# HDMI.net
KiCad netlist of a schematic drawn in Altium Designer
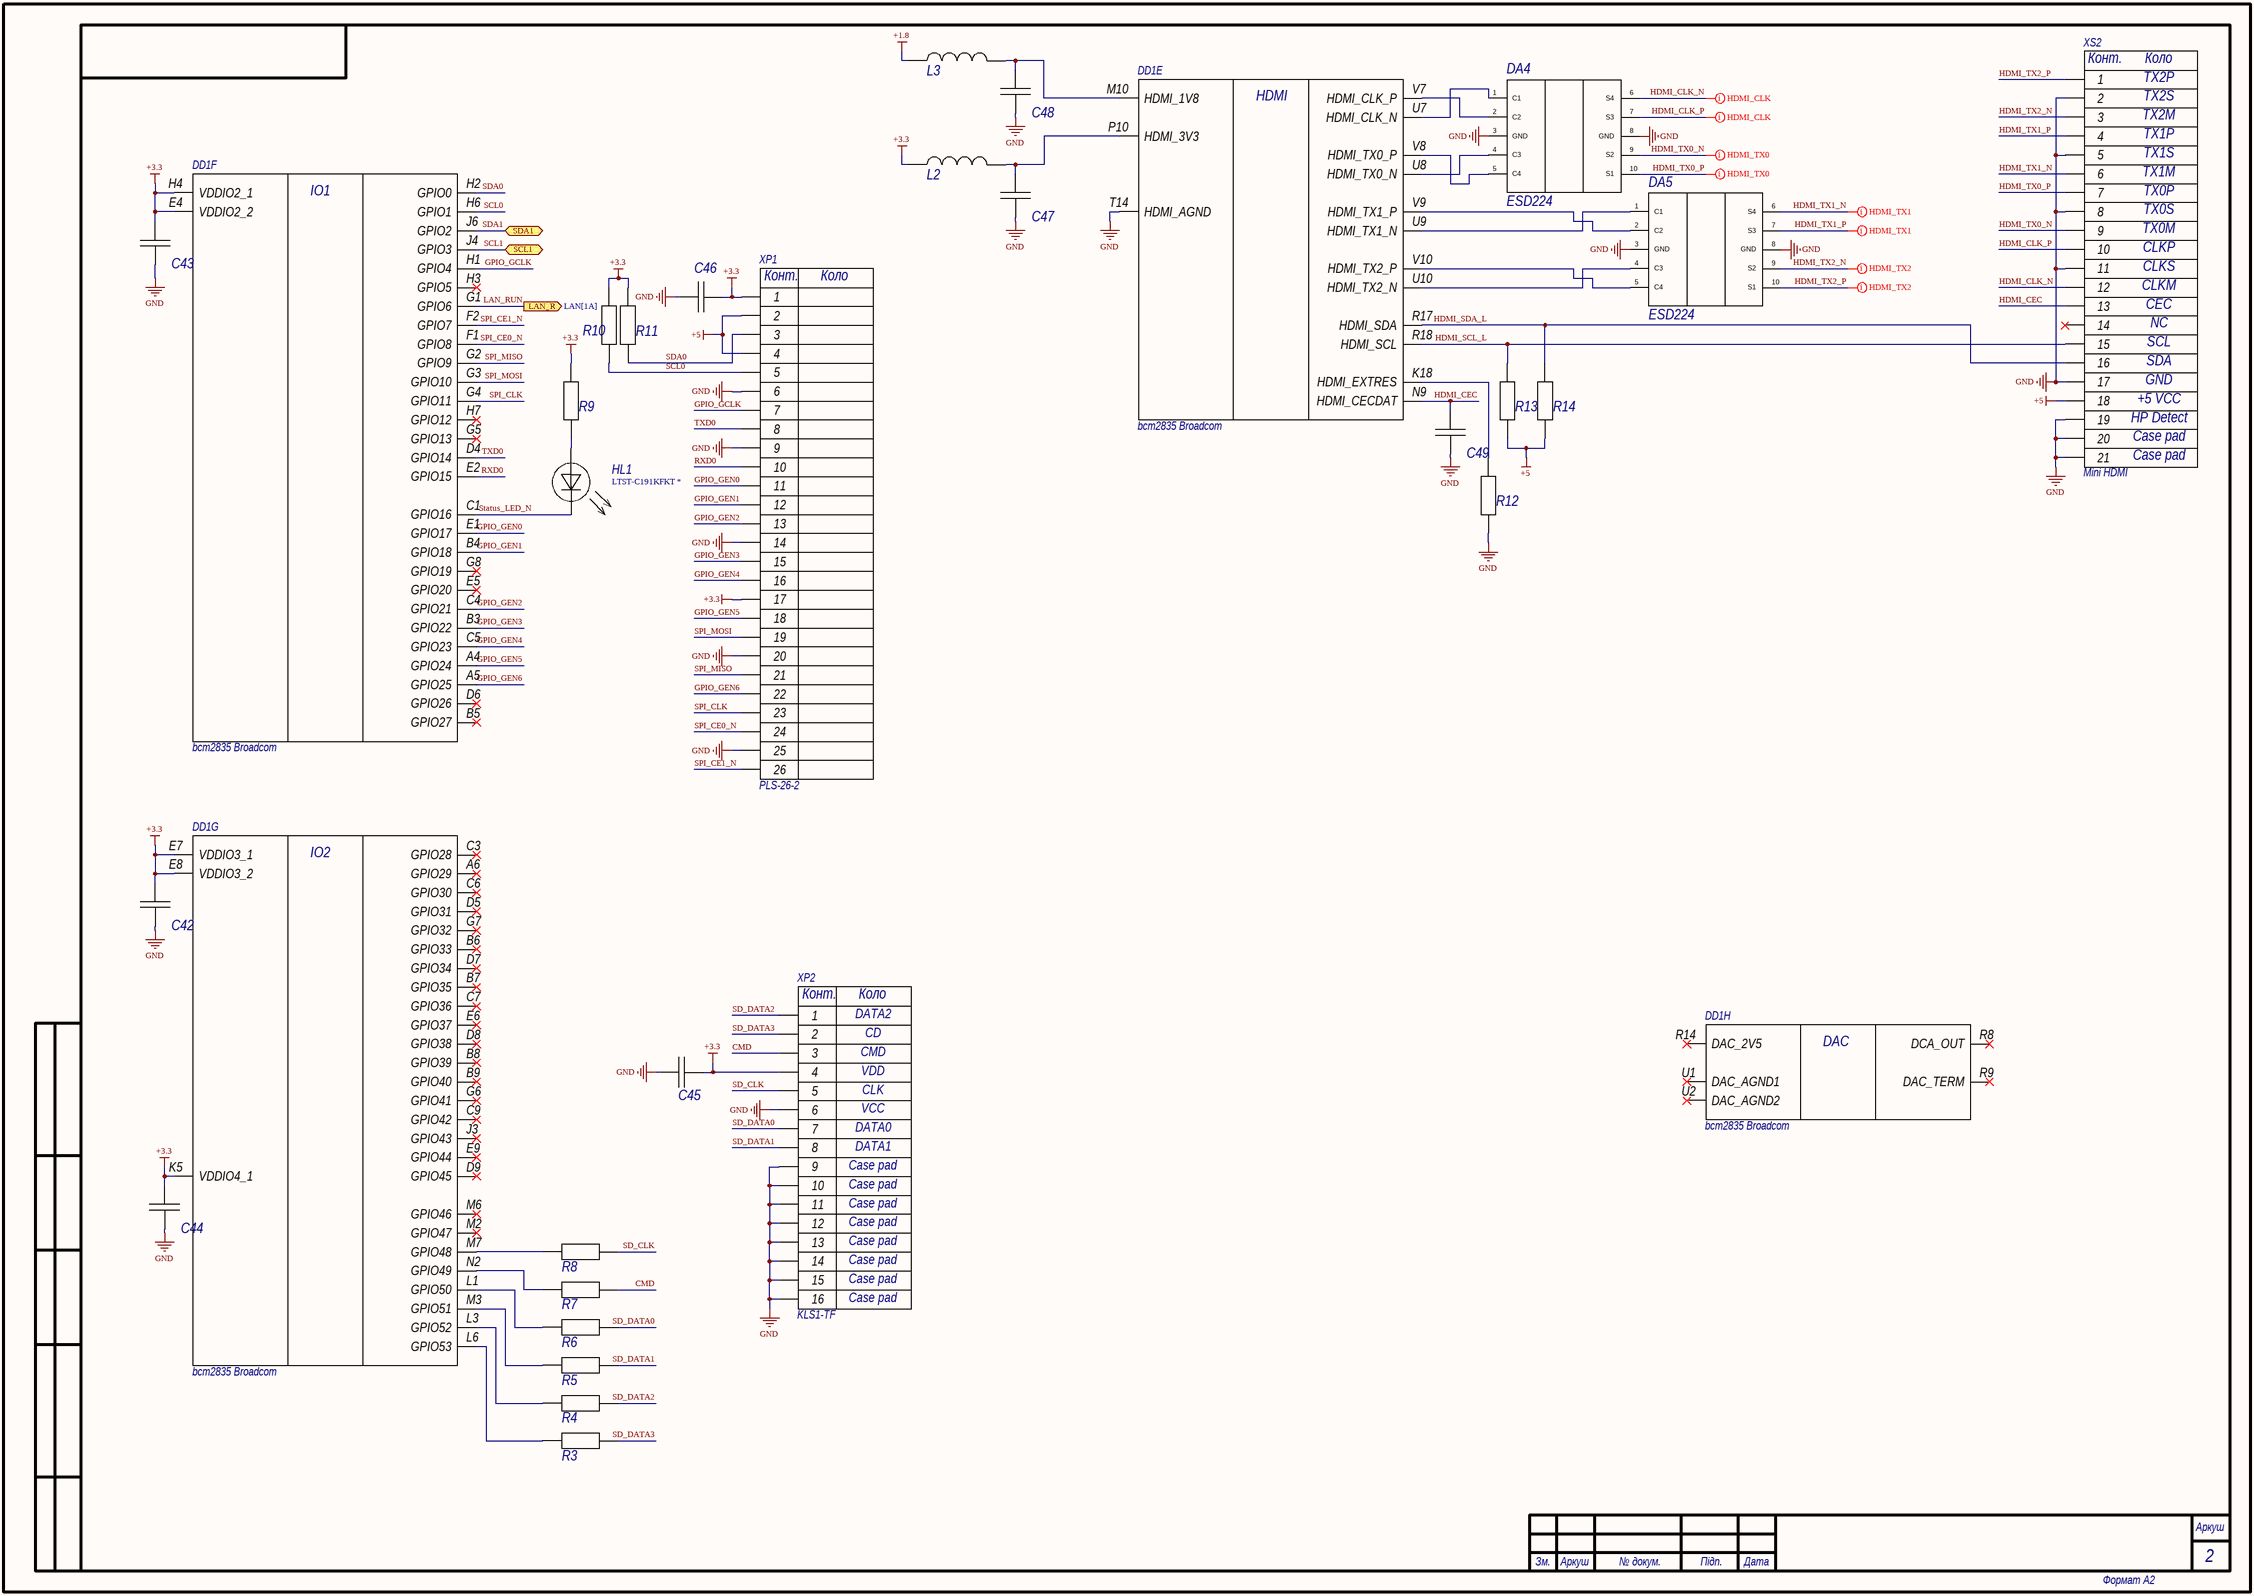
[diagram p0: HDMI.SchDoc]

(export (version "E")
  (design (tool "Eeschema 10.0.6"))
  (components
    (comp (ref "C42")
      (value "C-0603 * * * * *")
      (footprint "С-0603")
      (description "Generic")
      (libsource (lib "Schlib1") (part "С-0603"))
    )
    (comp (ref "C43")
      (value "C-0603 * * * * *")
      (footprint "С-0603")
      (description "Generic")
      (libsource (lib "Schlib1") (part "С-0603"))
    )
    (comp (ref "C44")
      (value "C-0603 * * * * *")
      (footprint "С-0603")
      (description "Generic")
      (libsource (lib "Schlib1") (part "С-0603"))
    )
    (comp (ref "C45")
      (value "C-0603 * * * * *")
      (footprint "С-0603")
      (description "Generic")
      (libsource (lib "Schlib1") (part "С-0603"))
    )
    (comp (ref "C46")
      (value "C-0603 * * * * *")
      (footprint "С-0603")
      (description "Generic")
      (libsource (lib "Schlib1") (part "С-0603"))
    )
    (comp (ref "C47")
      (value "C-0805 * * * * *")
      (footprint "C-0805-KEM")
      (description "Generic")
      (libsource (lib "Schlib1") (part "С-0805"))
    )
    (comp (ref "C48")
      (value "C-0805 * * * * *")
      (footprint "C-0805-KEM")
      (description "Generic")
      (libsource (lib "Schlib1") (part "С-0805"))
    )
    (comp (ref "C49")
      (value "C-0402 * * * * *")
      (footprint "C-0402")
      (description "Generic")
      (libsource (lib "Schlib1") (part "С-0402"))
    )
    (comp (ref "DA4")
      (value "ESD224 *")
      (footprint "DQA0010A")
      (description "bav99 double diode")
      (fields (field (name "NAME") "ESD224"))
      (libsource (lib "Schlib1") (part "ESD224"))
    )
    (comp (ref "DA5")
      (value "ESD224 *")
      (footprint "DQA0010A")
      (description "bav99 double diode")
      (fields (field (name "NAME") "ESD224"))
      (libsource (lib "Schlib1") (part "ESD224"))
    )
    (comp (ref "DD1")
      (value "bcm2835 Broadcom")
      (footprint "BGA81C65P18X18_1200X1200")
      (description "BCM2835 ARM-based processor")
      (fields (field (name "MANUFACTURER") "Broadcom"))
      (libsource (lib "Schlib1") (part "bcm2835"))
    )
    (comp (ref "HL1")
      (value "LTST-C191KFKT *")
      (footprint "LED_DIALIGHT_598_DIA")
      (description "Generic LED 0603")
      (libsource (lib "Schlib1") (part "LED 0603"))
    )
    (comp (ref "L2")
      (value "R-0402 * * * *")
      (footprint "FB-0805")
      (description "Generic")
      (libsource (lib "Schlib1") (part "Ferrite Bead 0805"))
    )
    (comp (ref "L3")
      (value "R-0402 * * * *")
      (footprint "FB-0805")
      (description "Generic")
      (libsource (lib "Schlib1") (part "Ferrite Bead 0805"))
    )
    (comp (ref "R3")
      (value "R-0603 * * * *")
      (footprint "R-0603")
      (description "Generic")
      (libsource (lib "Schlib1") (part "R-0603"))
    )
    (comp (ref "R4")
      (value "R-0603 * * * *")
      (footprint "R-0603")
      (description "Generic")
      (libsource (lib "Schlib1") (part "R-0603"))
    )
    (comp (ref "R5")
      (value "R-0603 * * * *")
      (footprint "R-0603")
      (description "Generic")
      (libsource (lib "Schlib1") (part "R-0603"))
    )
    (comp (ref "R6")
      (value "R-0603 * * * *")
      (footprint "R-0603")
      (description "Generic")
      (libsource (lib "Schlib1") (part "R-0603"))
    )
    (comp (ref "R7")
      (value "R-0603 * * * *")
      (footprint "R-0603")
      (description "Generic")
      (libsource (lib "Schlib1") (part "R-0603"))
    )
    (comp (ref "R8")
      (value "R-0603 * * * *")
      (footprint "R-0603")
      (description "Generic")
      (libsource (lib "Schlib1") (part "R-0603"))
    )
    (comp (ref "R9")
      (value "R-0603 * * * *")
      (footprint "R-0603")
      (description "Generic")
      (libsource (lib "") (part "R-0603_1"))
    )
    (comp (ref "R10")
      (value "R-0402 * * * *")
      (footprint "R-0402")
      (description "Generic")
      (libsource (lib "") (part "R-0402_1"))
    )
    (comp (ref "R11")
      (value "R-0402 * * * *")
      (footprint "R-0402")
      (description "Generic")
      (libsource (lib "") (part "R-0402_1"))
    )
    (comp (ref "R12")
      (value "R-0402 * * * *")
      (footprint "R-0402")
      (description "Generic")
      (libsource (lib "") (part "R-0402_1"))
    )
    (comp (ref "R13")
      (value "R-0402 * * * *")
      (footprint "R-0402")
      (description "Generic")
      (libsource (lib "Schlib1") (part "R-0402"))
    )
    (comp (ref "R14")
      (value "R-0402 * * * *")
      (footprint "R-0402")
      (description "Generic")
      (libsource (lib "Schlib1") (part "R-0402"))
    )
    (comp (ref "XP1")
      (value "PLS-26-2")
      (footprint "26 pin 2.54mm pitch 2 row")
      (description "PLS connector 26 pin 2.54mm pitch 2 rows")
      (libsource (lib "Schlib1") (part "PLS-26-2"))
    )
    (comp (ref "XP2")
      (value "KLS1-TF")
      (footprint "504077-1891_MOL")
      (description "Micro-SD card connector SMT mounting")
      (libsource (lib "Schlib1") (part "kls1-tf"))
    )
    (comp (ref "XS2")
      (value "Mini HDMI")
      (footprint "mini HDMI")
      (libsource (lib "Schlib1") (part "Mini HDMI"))
    )
  )
  (nets
    (net (code "1") (name "+1.8") (class "Default")
      (node (ref "L3") (pin "1") (pinfunction "1_1") (pintype "passive"))
    )
    (net (code "2") (name "+3.3") (class "Default")
      (node (ref "C42") (pin "1") (pinfunction "1_1") (pintype "passive"))
      (node (ref "C43") (pin "2") (pinfunction "2_2") (pintype "passive"))
      (node (ref "C44") (pin "1") (pinfunction "1_1") (pintype "passive"))
      (node (ref "C45") (pin "1") (pinfunction "1_1") (pintype "passive"))
      (node (ref "C46") (pin "2") (pinfunction "2_2") (pintype "passive"))
      (node (ref "DD1") (pin "E4") (pinfunction "VDDIO2_2_E4") (pintype "passive"))
      (node (ref "DD1") (pin "E7") (pinfunction "VDDIO3_1_E7") (pintype "passive"))
      (node (ref "DD1") (pin "E8") (pinfunction "VDDIO3_2_E8") (pintype "passive"))
      (node (ref "DD1") (pin "H4") (pinfunction "VDDIO2_1_H4") (pintype "passive"))
      (node (ref "DD1") (pin "K5") (pinfunction "VDDIO4_1_K5") (pintype "passive"))
      (node (ref "L2") (pin "1") (pinfunction "1_1") (pintype "passive"))
      (node (ref "R10") (pin "2") (pinfunction "2_2") (pintype "passive"))
      (node (ref "R11") (pin "2") (pinfunction "2_2") (pintype "passive"))
      (node (ref "R9") (pin "2") (pinfunction "2_2") (pintype "passive"))
      (node (ref "XP1") (pin "1") (pinfunction "1_1") (pintype "passive"))
      (node (ref "XP1") (pin "17") (pinfunction "17_17") (pintype "passive"))
      (node (ref "XP2") (pin "4") (pinfunction "4_4") (pintype "passive"))
    )
    (net (code "3") (name "+5") (class "Default")
      (node (ref "R13") (pin "2") (pinfunction "2_2") (pintype "passive"))
      (node (ref "R14") (pin "2") (pinfunction "2_2") (pintype "passive"))
      (node (ref "XP1") (pin "2") (pinfunction "2_2") (pintype "passive"))
      (node (ref "XP1") (pin "4") (pinfunction "4_4") (pintype "passive"))
      (node (ref "XS2") (pin "18") (pinfunction "18_18") (pintype "passive"))
    )
    (net (code "4") (name "/CMD") (class "Default")
      (node (ref "R7") (pin "2") (pinfunction "2_2") (pintype "passive"))
      (node (ref "XP2") (pin "3") (pinfunction "3_3") (pintype "passive"))
    )
    (net (code "5") (name "/GPIO_GCLK") (class "Default")
      (node (ref "DD1") (pin "H1") (pinfunction "GPIO4_H1") (pintype "passive"))
      (node (ref "XP1") (pin "7") (pinfunction "7_7") (pintype "passive"))
    )
    (net (code "6") (name "/GPIO_GEN0") (class "Default")
      (node (ref "DD1") (pin "E1") (pinfunction "GPIO17_E1") (pintype "passive"))
      (node (ref "XP1") (pin "11") (pinfunction "11_11") (pintype "passive"))
    )
    (net (code "7") (name "/GPIO_GEN1") (class "Default")
      (node (ref "DD1") (pin "B4") (pinfunction "GPIO18_B4") (pintype "passive"))
      (node (ref "XP1") (pin "12") (pinfunction "12_12") (pintype "passive"))
    )
    (net (code "8") (name "/GPIO_GEN2") (class "Default")
      (node (ref "DD1") (pin "C4") (pinfunction "GPIO21_C4") (pintype "passive"))
      (node (ref "XP1") (pin "13") (pinfunction "13_13") (pintype "passive"))
    )
    (net (code "9") (name "/GPIO_GEN3") (class "Default")
      (node (ref "DD1") (pin "B3") (pinfunction "GPIO22_B3") (pintype "passive"))
      (node (ref "XP1") (pin "15") (pinfunction "15_15") (pintype "passive"))
    )
    (net (code "10") (name "/GPIO_GEN4") (class "Default")
      (node (ref "DD1") (pin "C5") (pinfunction "GPIO23_C5") (pintype "passive"))
      (node (ref "XP1") (pin "16") (pinfunction "16_16") (pintype "passive"))
    )
    (net (code "11") (name "/GPIO_GEN5") (class "Default")
      (node (ref "DD1") (pin "A4") (pinfunction "GPIO24_A4") (pintype "passive"))
      (node (ref "XP1") (pin "18") (pinfunction "18_18") (pintype "passive"))
    )
    (net (code "12") (name "/GPIO_GEN6") (class "Default")
      (node (ref "DD1") (pin "A5") (pinfunction "GPIO25_A5") (pintype "passive"))
      (node (ref "XP1") (pin "22") (pinfunction "22_22") (pintype "passive"))
    )
    (net (code "13") (name "/HDMI_CEC") (class "Default")
      (node (ref "C49") (pin "2") (pinfunction "2_2") (pintype "passive"))
      (node (ref "DD1") (pin "N9") (pinfunction "HDMI_CECDAT_N9") (pintype "passive"))
      (node (ref "XS2") (pin "13") (pinfunction "13_13") (pintype "passive"))
    )
    (net (code "14") (name "/HDMI_CLK_N") (class "Default")
      (node (ref "DA4") (pin "6") (pinfunction "S4_6") (pintype "passive"))
      (node (ref "XS2") (pin "12") (pinfunction "12_12") (pintype "passive"))
    )
    (net (code "15") (name "/HDMI_CLK_P") (class "Default")
      (node (ref "DA4") (pin "7") (pinfunction "S3_7") (pintype "passive"))
      (node (ref "XS2") (pin "10") (pinfunction "10_10") (pintype "passive"))
    )
    (net (code "16") (name "/HDMI_SCL_L") (class "Default")
      (node (ref "DD1") (pin "R18") (pinfunction "HDMI_SCL_R18") (pintype "passive"))
      (node (ref "R13") (pin "1") (pinfunction "1_1") (pintype "passive"))
      (node (ref "XS2") (pin "15") (pinfunction "15_15") (pintype "passive"))
    )
    (net (code "17") (name "/HDMI_SDA_L") (class "Default")
      (node (ref "DD1") (pin "R17") (pinfunction "HDMI_SDA_R17") (pintype "passive"))
      (node (ref "R14") (pin "1") (pinfunction "1_1") (pintype "passive"))
      (node (ref "XS2") (pin "16") (pinfunction "16_16") (pintype "passive"))
    )
    (net (code "18") (name "/HDMI_TX0_N") (class "Default")
      (node (ref "DA4") (pin "9") (pinfunction "S2_9") (pintype "passive"))
      (node (ref "XS2") (pin "9") (pinfunction "9_9") (pintype "passive"))
    )
    (net (code "19") (name "/HDMI_TX0_P") (class "Default")
      (node (ref "DA4") (pin "10") (pinfunction "S1_10") (pintype "passive"))
      (node (ref "XS2") (pin "7") (pinfunction "7_7") (pintype "passive"))
    )
    (net (code "20") (name "/HDMI_TX1_N") (class "Default")
      (node (ref "DA5") (pin "6") (pinfunction "S4_6") (pintype "passive"))
      (node (ref "XS2") (pin "6") (pinfunction "6_6") (pintype "passive"))
    )
    (net (code "21") (name "/HDMI_TX1_P") (class "Default")
      (node (ref "DA5") (pin "7") (pinfunction "S3_7") (pintype "passive"))
      (node (ref "XS2") (pin "4") (pinfunction "4_4") (pintype "passive"))
    )
    (net (code "22") (name "/HDMI_TX2_N") (class "Default")
      (node (ref "DA5") (pin "9") (pinfunction "S2_9") (pintype "passive"))
      (node (ref "XS2") (pin "3") (pinfunction "3_3") (pintype "passive"))
    )
    (net (code "23") (name "/HDMI_TX2_P") (class "Default")
      (node (ref "DA5") (pin "10") (pinfunction "S1_10") (pintype "passive"))
      (node (ref "XS2") (pin "1") (pinfunction "1_1") (pintype "passive"))
    )
    (net (code "24") (name "/LAN_RUN") (class "Default")
      (node (ref "DD1") (pin "G1") (pinfunction "GPIO6_G1") (pintype "passive"))
    )
    (net (code "25") (name "/RXD0") (class "Default")
      (node (ref "DD1") (pin "E2") (pinfunction "GPIO15_E2") (pintype "passive"))
      (node (ref "XP1") (pin "10") (pinfunction "10_10") (pintype "passive"))
    )
    (net (code "26") (name "/SCL0") (class "Default")
      (node (ref "DD1") (pin "H6") (pinfunction "GPIO1_H6") (pintype "passive"))
      (node (ref "R10") (pin "1") (pinfunction "1_1") (pintype "passive"))
      (node (ref "XP1") (pin "5") (pinfunction "5_5") (pintype "passive"))
    )
    (net (code "27") (name "/SCL1") (class "Default")
      (node (ref "DD1") (pin "J4") (pinfunction "GPIO3_J4") (pintype "passive"))
    )
    (net (code "28") (name "/SDA0") (class "Default")
      (node (ref "DD1") (pin "H2") (pinfunction "GPIO0_H2") (pintype "passive"))
      (node (ref "R11") (pin "1") (pinfunction "1_1") (pintype "passive"))
      (node (ref "XP1") (pin "3") (pinfunction "3_3") (pintype "passive"))
    )
    (net (code "29") (name "/SDA1") (class "Default")
      (node (ref "DD1") (pin "J6") (pinfunction "GPIO2_J6") (pintype "passive"))
    )
    (net (code "30") (name "/SD_CLK") (class "Default")
      (node (ref "R8") (pin "2") (pinfunction "2_2") (pintype "passive"))
      (node (ref "XP2") (pin "5") (pinfunction "5_5") (pintype "passive"))
    )
    (net (code "31") (name "/SD_DATA0") (class "Default")
      (node (ref "R6") (pin "2") (pinfunction "2_2") (pintype "passive"))
      (node (ref "XP2") (pin "7") (pinfunction "7_7") (pintype "passive"))
    )
    (net (code "32") (name "/SD_DATA1") (class "Default")
      (node (ref "R5") (pin "2") (pinfunction "2_2") (pintype "passive"))
      (node (ref "XP2") (pin "8") (pinfunction "8_8") (pintype "passive"))
    )
    (net (code "33") (name "/SD_DATA2") (class "Default")
      (node (ref "R4") (pin "2") (pinfunction "2_2") (pintype "passive"))
      (node (ref "XP2") (pin "1") (pinfunction "1_1") (pintype "passive"))
    )
    (net (code "34") (name "/SD_DATA3") (class "Default")
      (node (ref "R3") (pin "2") (pinfunction "2_2") (pintype "passive"))
      (node (ref "XP2") (pin "2") (pinfunction "2_2") (pintype "passive"))
    )
    (net (code "35") (name "/SPI_CE0_N") (class "Default")
      (node (ref "DD1") (pin "F1") (pinfunction "GPIO8_F1") (pintype "passive"))
      (node (ref "XP1") (pin "24") (pinfunction "24_24") (pintype "passive"))
    )
    (net (code "36") (name "/SPI_CE1_N") (class "Default")
      (node (ref "DD1") (pin "F2") (pinfunction "GPIO7_F2") (pintype "passive"))
      (node (ref "XP1") (pin "26") (pinfunction "26_26") (pintype "passive"))
    )
    (net (code "37") (name "/SPI_CLK") (class "Default")
      (node (ref "DD1") (pin "G4") (pinfunction "GPIO11_G4") (pintype "passive"))
      (node (ref "XP1") (pin "23") (pinfunction "23_23") (pintype "passive"))
    )
    (net (code "38") (name "/SPI_MISO") (class "Default")
      (node (ref "DD1") (pin "G2") (pinfunction "GPIO9_G2") (pintype "passive"))
      (node (ref "XP1") (pin "21") (pinfunction "21_21") (pintype "passive"))
    )
    (net (code "39") (name "/SPI_MOSI") (class "Default")
      (node (ref "DD1") (pin "G3") (pinfunction "GPIO10_G3") (pintype "passive"))
      (node (ref "XP1") (pin "19") (pinfunction "19_19") (pintype "passive"))
    )
    (net (code "40") (name "/Status_LED_N") (class "Default")
      (node (ref "DD1") (pin "C1") (pinfunction "GPIO16_C1") (pintype "passive"))
      (node (ref "HL1") (pin "2") (pinfunction "2_2") (pintype "passive"))
    )
    (net (code "41") (name "/TXD0") (class "Default")
      (node (ref "DD1") (pin "D4") (pinfunction "GPIO14_D4") (pintype "passive"))
      (node (ref "XP1") (pin "8") (pinfunction "8_8") (pintype "passive"))
    )
    (net (code "42") (name "GND") (class "Default")
      (node (ref "C42") (pin "2") (pinfunction "2_2") (pintype "passive"))
      (node (ref "C43") (pin "1") (pinfunction "1_1") (pintype "passive"))
      (node (ref "C44") (pin "2") (pinfunction "2_2") (pintype "passive"))
      (node (ref "C45") (pin "2") (pinfunction "2_2") (pintype "passive"))
      (node (ref "C46") (pin "1") (pinfunction "1_1") (pintype "passive"))
      (node (ref "C47") (pin "2") (pinfunction "2_2") (pintype "passive"))
      (node (ref "C48") (pin "2") (pinfunction "2_2") (pintype "passive"))
      (node (ref "C49") (pin "1") (pinfunction "1_1") (pintype "passive"))
      (node (ref "DA4") (pin "3") (pinfunction "GND_3") (pintype "passive"))
      (node (ref "DA4") (pin "8") (pinfunction "GND_8") (pintype "passive"))
      (node (ref "DA5") (pin "3") (pinfunction "GND_3") (pintype "passive"))
      (node (ref "DA5") (pin "8") (pinfunction "GND_8") (pintype "passive"))
      (node (ref "DD1") (pin "T14") (pinfunction "HDMI_AGND_T14") (pintype "passive"))
      (node (ref "R12") (pin "1") (pinfunction "1_1") (pintype "passive"))
      (node (ref "XP1") (pin "14") (pinfunction "14_14") (pintype "passive"))
      (node (ref "XP1") (pin "20") (pinfunction "20_20") (pintype "passive"))
      (node (ref "XP1") (pin "25") (pinfunction "25_25") (pintype "passive"))
      (node (ref "XP1") (pin "6") (pinfunction "6_6") (pintype "passive"))
      (node (ref "XP1") (pin "9") (pinfunction "9_9") (pintype "passive"))
      (node (ref "XP2") (pin "10") (pinfunction "10_10") (pintype "passive"))
      (node (ref "XP2") (pin "11") (pinfunction "11_11") (pintype "passive"))
      (node (ref "XP2") (pin "12") (pinfunction "12_12") (pintype "passive"))
      (node (ref "XP2") (pin "13") (pinfunction "13_13") (pintype "passive"))
      (node (ref "XP2") (pin "14") (pinfunction "14_14") (pintype "passive"))
      (node (ref "XP2") (pin "15") (pinfunction "15_15") (pintype "passive"))
      (node (ref "XP2") (pin "16") (pinfunction "16_16") (pintype "passive"))
      (node (ref "XP2") (pin "6") (pinfunction "6_6") (pintype "passive"))
      (node (ref "XP2") (pin "9") (pinfunction "9_9") (pintype "passive"))
      (node (ref "XS2") (pin "11") (pinfunction "11_11") (pintype "passive"))
      (node (ref "XS2") (pin "17") (pinfunction "17_17") (pintype "passive"))
      (node (ref "XS2") (pin "19") (pinfunction "19_19") (pintype "passive"))
      (node (ref "XS2") (pin "2") (pinfunction "2_2") (pintype "passive"))
      (node (ref "XS2") (pin "20") (pinfunction "20_20") (pintype "passive"))
      (node (ref "XS2") (pin "21") (pinfunction "21_21") (pintype "passive"))
      (node (ref "XS2") (pin "5") (pinfunction "5_5") (pintype "passive"))
      (node (ref "XS2") (pin "8") (pinfunction "8_8") (pintype "passive"))
    )
    (net (code "43") (name "Net-(DA4-C1)") (class "Default")
      (node (ref "DA4") (pin "1") (pinfunction "C1_1") (pintype "passive"))
      (node (ref "DD1") (pin "U7") (pinfunction "HDMI_CLK_N_U7") (pintype "passive"))
    )
    (net (code "44") (name "Net-(DA4-C2)") (class "Default")
      (node (ref "DA4") (pin "2") (pinfunction "C2_2") (pintype "passive"))
      (node (ref "DD1") (pin "V7") (pinfunction "HDMI_CLK_P_V7") (pintype "passive"))
    )
    (net (code "45") (name "Net-(DA4-C3)") (class "Default")
      (node (ref "DA4") (pin "4") (pinfunction "C3_4") (pintype "passive"))
      (node (ref "DD1") (pin "U8") (pinfunction "HDMI_TX0_N_U8") (pintype "passive"))
    )
    (net (code "46") (name "Net-(DA4-C4)") (class "Default")
      (node (ref "DA4") (pin "5") (pinfunction "C4_5") (pintype "passive"))
      (node (ref "DD1") (pin "V8") (pinfunction "HDMI_TX0_P_V8") (pintype "passive"))
    )
    (net (code "47") (name "Net-(DA5-C1)") (class "Default")
      (node (ref "DA5") (pin "1") (pinfunction "C1_1") (pintype "passive"))
      (node (ref "DD1") (pin "U9") (pinfunction "HDMI_TX1_N_U9") (pintype "passive"))
    )
    (net (code "48") (name "Net-(DA5-C2)") (class "Default")
      (node (ref "DA5") (pin "2") (pinfunction "C2_2") (pintype "passive"))
      (node (ref "DD1") (pin "V9") (pinfunction "HDMI_TX1_P_V9") (pintype "passive"))
    )
    (net (code "49") (name "Net-(DA5-C3)") (class "Default")
      (node (ref "DA5") (pin "4") (pinfunction "C3_4") (pintype "passive"))
      (node (ref "DD1") (pin "U10") (pinfunction "HDMI_TX2_N_U10") (pintype "passive"))
    )
    (net (code "50") (name "Net-(DA5-C4)") (class "Default")
      (node (ref "DA5") (pin "5") (pinfunction "C4_5") (pintype "passive"))
      (node (ref "DD1") (pin "V10") (pinfunction "HDMI_TX2_P_V10") (pintype "passive"))
    )
    (net (code "51") (name "Net-(DD1E-HDMI_1V8)") (class "Default")
      (node (ref "C48") (pin "1") (pinfunction "1_1") (pintype "passive"))
      (node (ref "DD1") (pin "M10") (pinfunction "HDMI_1V8_M10") (pintype "passive"))
      (node (ref "L3") (pin "2") (pinfunction "2_2") (pintype "passive"))
    )
    (net (code "52") (name "Net-(DD1E-HDMI_3V3)") (class "Default")
      (node (ref "C47") (pin "1") (pinfunction "1_1") (pintype "passive"))
      (node (ref "DD1") (pin "P10") (pinfunction "HDMI_3V3_P10") (pintype "passive"))
      (node (ref "L2") (pin "2") (pinfunction "2_2") (pintype "passive"))
    )
    (net (code "53") (name "Net-(DD1E-HDMI_EXTRES)") (class "Default")
      (node (ref "DD1") (pin "K18") (pinfunction "HDMI_EXTRES_K18") (pintype "passive"))
      (node (ref "R12") (pin "2") (pinfunction "2_2") (pintype "passive"))
    )
    (net (code "54") (name "Net-(DD1G-GPIO48)") (class "Default")
      (node (ref "DD1") (pin "M7") (pinfunction "GPIO48_M7") (pintype "passive"))
      (node (ref "R8") (pin "1") (pinfunction "1_1") (pintype "passive"))
    )
    (net (code "55") (name "Net-(DD1G-GPIO49)") (class "Default")
      (node (ref "DD1") (pin "N2") (pinfunction "GPIO49_N2") (pintype "passive"))
      (node (ref "R7") (pin "1") (pinfunction "1_1") (pintype "passive"))
    )
    (net (code "56") (name "Net-(DD1G-GPIO50)") (class "Default")
      (node (ref "DD1") (pin "L1") (pinfunction "GPIO50_L1") (pintype "passive"))
      (node (ref "R6") (pin "1") (pinfunction "1_1") (pintype "passive"))
    )
    (net (code "57") (name "Net-(DD1G-GPIO51)") (class "Default")
      (node (ref "DD1") (pin "M3") (pinfunction "GPIO51_M3") (pintype "passive"))
      (node (ref "R5") (pin "1") (pinfunction "1_1") (pintype "passive"))
    )
    (net (code "58") (name "Net-(DD1G-GPIO52)") (class "Default")
      (node (ref "DD1") (pin "L3") (pinfunction "GPIO52_L3") (pintype "passive"))
      (node (ref "R4") (pin "1") (pinfunction "1_1") (pintype "passive"))
    )
    (net (code "59") (name "Net-(DD1G-GPIO53)") (class "Default")
      (node (ref "DD1") (pin "L6") (pinfunction "GPIO53_L6") (pintype "passive"))
      (node (ref "R3") (pin "1") (pinfunction "1_1") (pintype "passive"))
    )
    (net (code "60") (name "Net-(HL1-Pad1)") (class "Default")
      (node (ref "HL1") (pin "1") (pinfunction "1_1") (pintype "passive"))
      (node (ref "R9") (pin "1") (pinfunction "1_1") (pintype "passive"))
    )
    (net (code "61") (name "unconnected-(DD1F-GPIO5-PadH3)") (class "Default")
      (node (ref "DD1") (pin "H3") (pinfunction "GPIO5_H3") (pintype "passive+no_connect"))
    )
    (net (code "62") (name "unconnected-(DD1F-GPIO12-PadH7)") (class "Default")
      (node (ref "DD1") (pin "H7") (pinfunction "GPIO12_H7") (pintype "passive+no_connect"))
    )
    (net (code "63") (name "unconnected-(DD1F-GPIO13-PadG5)") (class "Default")
      (node (ref "DD1") (pin "G5") (pinfunction "GPIO13_G5") (pintype "passive+no_connect"))
    )
    (net (code "64") (name "unconnected-(DD1F-GPIO19-PadG8)") (class "Default")
      (node (ref "DD1") (pin "G8") (pinfunction "GPIO19_G8") (pintype "passive+no_connect"))
    )
    (net (code "65") (name "unconnected-(DD1F-GPIO20-PadE5)") (class "Default")
      (node (ref "DD1") (pin "E5") (pinfunction "GPIO20_E5") (pintype "passive+no_connect"))
    )
    (net (code "66") (name "unconnected-(DD1F-GPIO26-PadD6)") (class "Default")
      (node (ref "DD1") (pin "D6") (pinfunction "GPIO26_D6") (pintype "passive+no_connect"))
    )
    (net (code "67") (name "unconnected-(DD1F-GPIO27-PadB5)") (class "Default")
      (node (ref "DD1") (pin "B5") (pinfunction "GPIO27_B5") (pintype "passive+no_connect"))
    )
    (net (code "68") (name "unconnected-(DD1G-GPIO28-PadC3)") (class "Default")
      (node (ref "DD1") (pin "C3") (pinfunction "GPIO28_C3") (pintype "passive+no_connect"))
    )
    (net (code "69") (name "unconnected-(DD1G-GPIO29-PadA6)") (class "Default")
      (node (ref "DD1") (pin "A6") (pinfunction "GPIO29_A6") (pintype "passive+no_connect"))
    )
    (net (code "70") (name "unconnected-(DD1G-GPIO30-PadC6)") (class "Default")
      (node (ref "DD1") (pin "C6") (pinfunction "GPIO30_C6") (pintype "passive+no_connect"))
    )
    (net (code "71") (name "unconnected-(DD1G-GPIO31-PadD5)") (class "Default")
      (node (ref "DD1") (pin "D5") (pinfunction "GPIO31_D5") (pintype "passive+no_connect"))
    )
    (net (code "72") (name "unconnected-(DD1G-GPIO32-PadG7)") (class "Default")
      (node (ref "DD1") (pin "G7") (pinfunction "GPIO32_G7") (pintype "passive+no_connect"))
    )
    (net (code "73") (name "unconnected-(DD1G-GPIO33-PadB6)") (class "Default")
      (node (ref "DD1") (pin "B6") (pinfunction "GPIO33_B6") (pintype "passive+no_connect"))
    )
    (net (code "74") (name "unconnected-(DD1G-GPIO34-PadD7)") (class "Default")
      (node (ref "DD1") (pin "D7") (pinfunction "GPIO34_D7") (pintype "passive+no_connect"))
    )
    (net (code "75") (name "unconnected-(DD1G-GPIO35-PadB7)") (class "Default")
      (node (ref "DD1") (pin "B7") (pinfunction "GPIO35_B7") (pintype "passive+no_connect"))
    )
    (net (code "76") (name "unconnected-(DD1G-GPIO36-PadC7)") (class "Default")
      (node (ref "DD1") (pin "C7") (pinfunction "GPIO36_C7") (pintype "passive+no_connect"))
    )
    (net (code "77") (name "unconnected-(DD1G-GPIO37-PadE6)") (class "Default")
      (node (ref "DD1") (pin "E6") (pinfunction "GPIO37_E6") (pintype "passive+no_connect"))
    )
    (net (code "78") (name "unconnected-(DD1G-GPIO38-PadD8)") (class "Default")
      (node (ref "DD1") (pin "D8") (pinfunction "GPIO38_D8") (pintype "passive+no_connect"))
    )
    (net (code "79") (name "unconnected-(DD1G-GPIO39-PadB8)") (class "Default")
      (node (ref "DD1") (pin "B8") (pinfunction "GPIO39_B8") (pintype "passive+no_connect"))
    )
    (net (code "80") (name "unconnected-(DD1G-GPIO40-PadB9)") (class "Default")
      (node (ref "DD1") (pin "B9") (pinfunction "GPIO40_B9") (pintype "passive+no_connect"))
    )
    (net (code "81") (name "unconnected-(DD1G-GPIO41-PadG6)") (class "Default")
      (node (ref "DD1") (pin "G6") (pinfunction "GPIO41_G6") (pintype "passive+no_connect"))
    )
    (net (code "82") (name "unconnected-(DD1G-GPIO42-PadC9)") (class "Default")
      (node (ref "DD1") (pin "C9") (pinfunction "GPIO42_C9") (pintype "passive+no_connect"))
    )
    (net (code "83") (name "unconnected-(DD1G-GPIO43-PadJ3)") (class "Default")
      (node (ref "DD1") (pin "J3") (pinfunction "GPIO43_J3") (pintype "passive+no_connect"))
    )
    (net (code "84") (name "unconnected-(DD1G-GPIO44-PadE9)") (class "Default")
      (node (ref "DD1") (pin "E9") (pinfunction "GPIO44_E9") (pintype "passive+no_connect"))
    )
    (net (code "85") (name "unconnected-(DD1G-GPIO45-PadD9)") (class "Default")
      (node (ref "DD1") (pin "D9") (pinfunction "GPIO45_D9") (pintype "passive+no_connect"))
    )
    (net (code "86") (name "unconnected-(DD1G-GPIO46-PadM6)") (class "Default")
      (node (ref "DD1") (pin "M6") (pinfunction "GPIO46_M6") (pintype "passive+no_connect"))
    )
    (net (code "87") (name "unconnected-(DD1G-GPIO47-PadM2)") (class "Default")
      (node (ref "DD1") (pin "M2") (pinfunction "GPIO47_M2") (pintype "passive+no_connect"))
    )
    (net (code "88") (name "unconnected-(DD1H-DAC_2V5-PadR14)") (class "Default")
      (node (ref "DD1") (pin "R14") (pinfunction "DAC_2V5_R14") (pintype "passive+no_connect"))
    )
    (net (code "89") (name "unconnected-(DD1H-DAC_AGND1-PadU1)") (class "Default")
      (node (ref "DD1") (pin "U1") (pinfunction "DAC_AGND1_U1") (pintype "passive+no_connect"))
    )
    (net (code "90") (name "unconnected-(DD1H-DAC_AGND2-PadU2)") (class "Default")
      (node (ref "DD1") (pin "U2") (pinfunction "DAC_AGND2_U2") (pintype "passive+no_connect"))
    )
    (net (code "91") (name "unconnected-(DD1H-DAC_TERM-PadR9)") (class "Default")
      (node (ref "DD1") (pin "R9") (pinfunction "DAC_TERM_R9") (pintype "passive+no_connect"))
    )
    (net (code "92") (name "unconnected-(DD1H-DCA_OUT-PadR8)") (class "Default")
      (node (ref "DD1") (pin "R8") (pinfunction "DCA_OUT_R8") (pintype "passive+no_connect"))
    )
    (net (code "93") (name "unconnected-(XS2-Pad14)") (class "Default")
      (node (ref "XS2") (pin "14") (pinfunction "14_14") (pintype "passive+no_connect"))
    )
  )
)
